# blinky.net
KiCad netlist of a schematic drawn in EAGLE
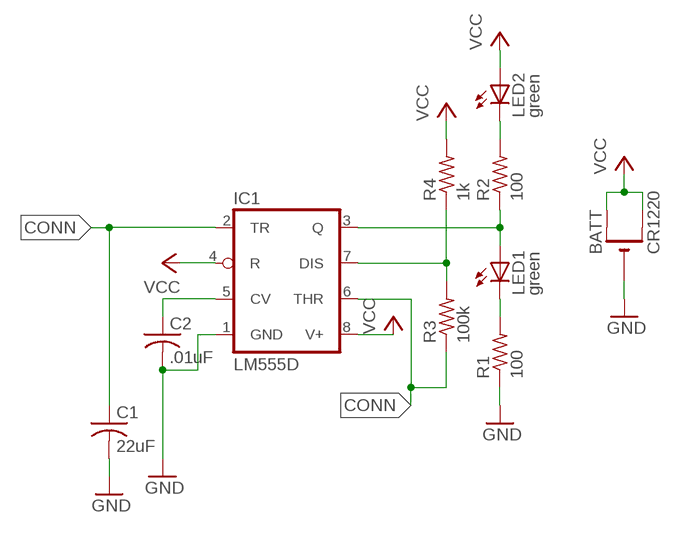
[diagram p0: schematic, sheet 1]

(export (version "E")
  (design (tool "Eeschema 10.0.6"))
  (components
    (comp (ref "BATT")
      (value "CR1220")
      (footprint "eagle-import:CR1220-SMD")
      (libsource (lib "eagle-import") (part "CR1220SMT"))
    )
    (comp (ref "C1")
      (value "22uF")
      (footprint "eagle-import:C0805")
      (libsource (lib "eagle-import") (part "C-USC0805"))
    )
    (comp (ref "C2")
      (value ".01uF")
      (footprint "eagle-import:C0805")
      (libsource (lib "eagle-import") (part "C-USC0805"))
    )
    (comp (ref "IC1")
      (value "LM555D")
      (footprint "eagle-import:SO08")
      (libsource (lib "eagle-import") (part "555DLM"))
    )
    (comp (ref "LED1")
      (value "green")
      (footprint "eagle-import:CHIPLED_0805")
      (libsource (lib "eagle-import") (part "LEDCHIPLED_0805"))
    )
    (comp (ref "LED2")
      (value "green")
      (footprint "eagle-import:CHIPLED_0805")
      (libsource (lib "eagle-import") (part "LEDCHIPLED_0805"))
    )
    (comp (ref "R1")
      (value "100")
      (footprint "eagle-import:R0805")
      (libsource (lib "eagle-import") (part "R-US_R0805"))
    )
    (comp (ref "R2")
      (value "100")
      (footprint "eagle-import:R0805")
      (libsource (lib "eagle-import") (part "R-US_R0805"))
    )
    (comp (ref "R3")
      (value "100k")
      (footprint "eagle-import:R0805")
      (libsource (lib "eagle-import") (part "R-US_R0805"))
    )
    (comp (ref "R4")
      (value "1k")
      (footprint "eagle-import:R0805")
      (libsource (lib "eagle-import") (part "R-US_R0805"))
    )
  )
  (nets
    (net (code "1") (name "CONN") (class "Default")
      (node (ref "C1") (pin "1") (pinfunction "1_1") (pintype "passive"))
      (node (ref "IC1") (pin "2") (pinfunction "TR_2") (pintype "input"))
      (node (ref "IC1") (pin "6") (pinfunction "THR_6") (pintype "input"))
      (node (ref "R3") (pin "1") (pinfunction "1_1") (pintype "passive"))
    )
    (net (code "2") (name "GND") (class "Default")
      (node (ref "BATT") (pin "-") (pinfunction "-_-") (pintype "passive"))
      (node (ref "C1") (pin "2") (pinfunction "2_2") (pintype "passive"))
      (node (ref "C2") (pin "2") (pinfunction "2_2") (pintype "passive"))
      (node (ref "IC1") (pin "1") (pinfunction "GND_1") (pintype "power_in"))
      (node (ref "R1") (pin "1") (pinfunction "1_1") (pintype "passive"))
    )
    (net (code "3") (name "Net-(IC1-CV)") (class "Default")
      (node (ref "C2") (pin "1") (pinfunction "1_1") (pintype "passive"))
      (node (ref "IC1") (pin "5") (pinfunction "CV_5") (pintype "input"))
    )
    (net (code "4") (name "Net-(IC1-DIS)") (class "Default")
      (node (ref "IC1") (pin "7") (pinfunction "DIS_7") (pintype "input"))
      (node (ref "R3") (pin "2") (pinfunction "2_2") (pintype "passive"))
      (node (ref "R4") (pin "1") (pinfunction "1_1") (pintype "passive"))
    )
    (net (code "5") (name "Net-(IC1-Q)") (class "Default")
      (node (ref "IC1") (pin "3") (pinfunction "Q_3") (pintype "output"))
      (node (ref "LED1") (pin "A") (pinfunction "A_A") (pintype "passive"))
      (node (ref "R2") (pin "1") (pinfunction "1_1") (pintype "passive"))
    )
    (net (code "6") (name "Net-(LED1-PadC)") (class "Default")
      (node (ref "LED1") (pin "C") (pinfunction "C_C") (pintype "passive"))
      (node (ref "R1") (pin "2") (pinfunction "2_2") (pintype "passive"))
    )
    (net (code "7") (name "Net-(LED2-PadC)") (class "Default")
      (node (ref "LED2") (pin "C") (pinfunction "C_C") (pintype "passive"))
      (node (ref "R2") (pin "2") (pinfunction "2_2") (pintype "passive"))
    )
    (net (code "8") (name "VCC") (class "Default")
      (node (ref "BATT") (pin "+$1") (pinfunction "+_+$1") (pintype "passive"))
      (node (ref "BATT") (pin "+$2") (pinfunction "+1_+$2") (pintype "passive"))
      (node (ref "IC1") (pin "4") (pinfunction "R_4") (pintype "input"))
      (node (ref "IC1") (pin "8") (pinfunction "V+_8") (pintype "power_in"))
      (node (ref "LED2") (pin "A") (pinfunction "A_A") (pintype "passive"))
      (node (ref "R4") (pin "2") (pinfunction "2_2") (pintype "passive"))
    )
  )
)
